# DAC_PART.net
KiCad netlist of a schematic drawn in Altium Designer
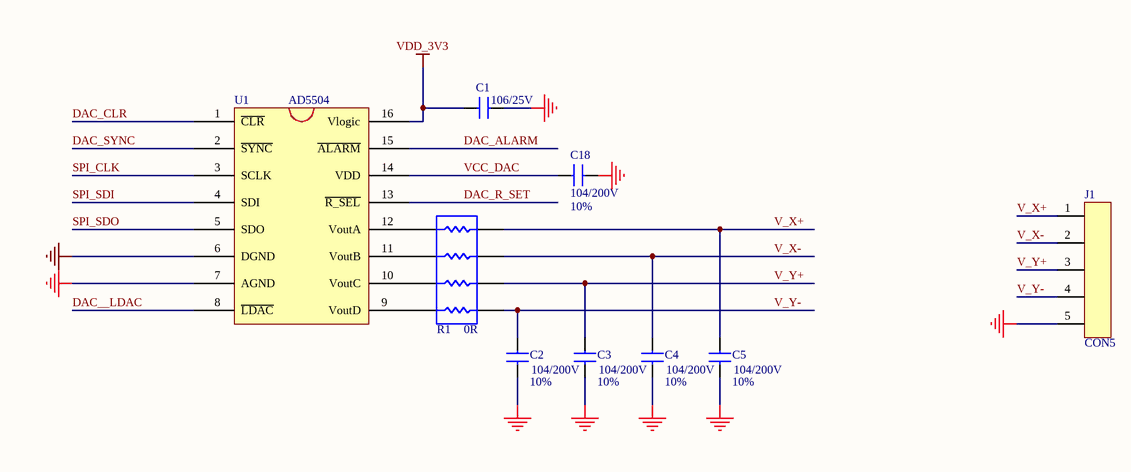
[diagram p0: DAC_PART.SchDoc]

(export (version "E")
  (design (tool "Eeschema 10.0.6"))
  (components
    (comp (ref "C1")
      (value "106/25V")
      (footprint "0603C/1")
      (description "Capacitor")
      (libsource (lib "其他常用器件") (part "电容"))
    )
    (comp (ref "C2")
      (value "104/200V")
      (footprint "0805C")
      (description "Capacitor")
      (fields (field (name "ALTIUM_UNNAMED_1") "10%"))
      (libsource (lib "其他常用器件") (part "电容"))
    )
    (comp (ref "C3")
      (value "104/200V")
      (footprint "0805C")
      (description "Capacitor")
      (fields (field (name "ALTIUM_UNNAMED_1") "10%"))
      (libsource (lib "其他常用器件") (part "电容"))
    )
    (comp (ref "C4")
      (value "104/200V")
      (footprint "0805C")
      (description "Capacitor")
      (fields (field (name "ALTIUM_UNNAMED_1") "10%"))
      (libsource (lib "其他常用器件") (part "电容"))
    )
    (comp (ref "C5")
      (value "104/200V")
      (footprint "0805C")
      (description "Capacitor")
      (fields (field (name "ALTIUM_UNNAMED_1") "10%"))
      (libsource (lib "其他常用器件") (part "电容"))
    )
    (comp (ref "C18")
      (value "104/200V")
      (footprint "0805C")
      (description "Capacitor")
      (fields (field (name "ALTIUM_UNNAMED_1") "10%"))
      (libsource (lib "其他常用器件") (part "电容"))
    )
    (comp (ref "J1")
      (value "CON5")
      (footprint "DUT_1XN_1.2_2.0")
      (description "SOCKET")
      (libsource (lib "其他常用器件") (part "CON5"))
    )
    (comp (ref "R1") (value "0R") (footprint "4R0603/1") (libsource (lib "其他常用器件") (part "RES4/1")))
    (comp (ref "U1")
      (value "AD5504")
      (footprint "TSSOP-16_L5.0-W4.4-P0.65-LS6.4-BL")
      (libsource (lib "其他常用器件") (part "AD5504"))
    )
  )
  (nets
    (net (code "1") (name "/DAC_ALARM") (class "Default")
      (node (ref "U1") (pin "15") (pinfunction "~{ALARM}_15") (pintype "passive"))
    )
    (net (code "2") (name "/DAC_CLR") (class "Default")
      (node (ref "U1") (pin "1") (pinfunction "~{CLR}_1") (pintype "passive"))
    )
    (net (code "3") (name "/DAC_R_SET") (class "Default")
      (node (ref "U1") (pin "13") (pinfunction "~{R_SEL}_13") (pintype "passive"))
    )
    (net (code "4") (name "/DAC_SYNC") (class "Default")
      (node (ref "U1") (pin "2") (pinfunction "~{SYNC}_2") (pintype "passive"))
    )
    (net (code "5") (name "/DAC__LDAC") (class "Default")
      (node (ref "U1") (pin "8") (pinfunction "~{LDAC}_8") (pintype "passive"))
    )
    (net (code "6") (name "/SPI_CLK") (class "Default")
      (node (ref "U1") (pin "3") (pinfunction "SCLK_3") (pintype "passive"))
    )
    (net (code "7") (name "/SPI_SDI") (class "Default")
      (node (ref "U1") (pin "4") (pinfunction "SDI_4") (pintype "passive"))
    )
    (net (code "8") (name "/SPI_SDO") (class "Default")
      (node (ref "U1") (pin "5") (pinfunction "SDO_5") (pintype "passive"))
    )
    (net (code "9") (name "/VCC_DAC") (class "Default")
      (node (ref "C18") (pin "2") (pinfunction "2_2") (pintype "passive"))
      (node (ref "U1") (pin "14") (pinfunction "VDD_14") (pintype "passive"))
    )
    (net (code "10") (name "/V_X+") (class "Default")
      (node (ref "C5") (pin "2") (pinfunction "2_2") (pintype "passive"))
      (node (ref "J1") (pin "1") (pinfunction "1_1") (pintype "passive"))
      (node (ref "R1") (pin "2") (pinfunction "2_2") (pintype "passive"))
    )
    (net (code "11") (name "/V_X-") (class "Default")
      (node (ref "C4") (pin "2") (pinfunction "2_2") (pintype "passive"))
      (node (ref "J1") (pin "2") (pinfunction "2_2") (pintype "passive"))
      (node (ref "R1") (pin "4") (pinfunction "4_4") (pintype "passive"))
    )
    (net (code "12") (name "/V_Y+") (class "Default")
      (node (ref "C3") (pin "2") (pinfunction "2_2") (pintype "passive"))
      (node (ref "J1") (pin "3") (pinfunction "3_3") (pintype "passive"))
      (node (ref "R1") (pin "6") (pinfunction "6_6") (pintype "passive"))
    )
    (net (code "13") (name "/V_Y-") (class "Default")
      (node (ref "C2") (pin "2") (pinfunction "2_2") (pintype "passive"))
      (node (ref "J1") (pin "4") (pinfunction "4_4") (pintype "passive"))
      (node (ref "R1") (pin "8") (pinfunction "8_8") (pintype "passive"))
    )
    (net (code "14") (name "GND") (class "Default")
      (node (ref "C1") (pin "1") (pinfunction "1_1") (pintype "passive"))
      (node (ref "C18") (pin "1") (pinfunction "1_1") (pintype "passive"))
      (node (ref "C2") (pin "1") (pinfunction "1_1") (pintype "passive"))
      (node (ref "C3") (pin "1") (pinfunction "1_1") (pintype "passive"))
      (node (ref "C4") (pin "1") (pinfunction "1_1") (pintype "passive"))
      (node (ref "C5") (pin "1") (pinfunction "1_1") (pintype "passive"))
      (node (ref "J1") (pin "5") (pinfunction "5_5") (pintype "passive"))
      (node (ref "U1") (pin "6") (pinfunction "DGND_6") (pintype "passive"))
      (node (ref "U1") (pin "7") (pinfunction "AGND_7") (pintype "passive"))
    )
    (net (code "15") (name "Net-(U1-VoutA)") (class "Default")
      (node (ref "R1") (pin "1") (pinfunction "1_1") (pintype "passive"))
      (node (ref "U1") (pin "12") (pinfunction "VoutA_12") (pintype "passive"))
    )
    (net (code "16") (name "Net-(U1-VoutB)") (class "Default")
      (node (ref "R1") (pin "3") (pinfunction "3_3") (pintype "passive"))
      (node (ref "U1") (pin "11") (pinfunction "VoutB_11") (pintype "passive"))
    )
    (net (code "17") (name "Net-(U1-VoutC)") (class "Default")
      (node (ref "R1") (pin "5") (pinfunction "5_5") (pintype "passive"))
      (node (ref "U1") (pin "10") (pinfunction "VoutC_10") (pintype "passive"))
    )
    (net (code "18") (name "Net-(U1-VoutD)") (class "Default")
      (node (ref "R1") (pin "7") (pinfunction "7_7") (pintype "passive"))
      (node (ref "U1") (pin "9") (pinfunction "VoutD_9") (pintype "passive"))
    )
    (net (code "19") (name "VDD_3V3") (class "Default")
      (node (ref "C1") (pin "2") (pinfunction "2_2") (pintype "passive"))
      (node (ref "U1") (pin "16") (pinfunction "Vlogic_16") (pintype "passive"))
    )
  )
)
